# crowbar.net
KiCad netlist of a schematic drawn in Altium Designer
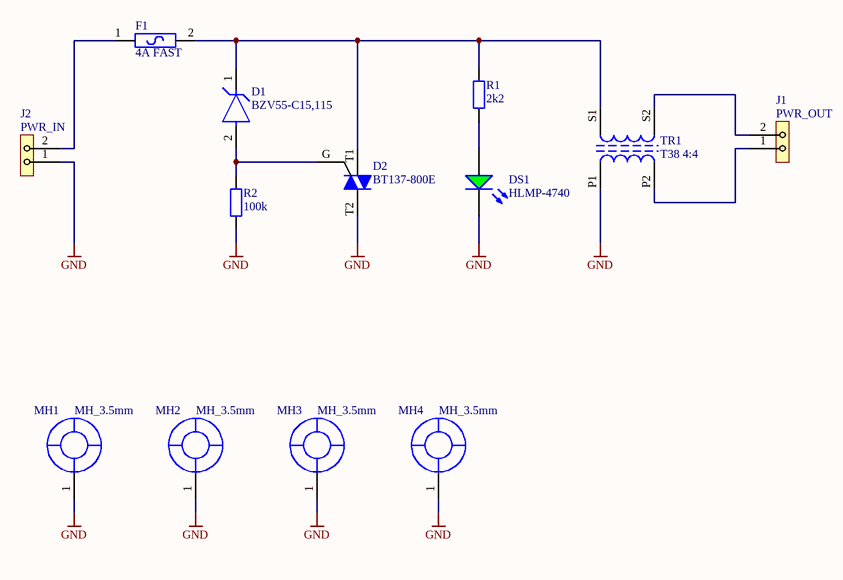
[diagram p0: crowbar.SchDoc]

(export (version "E")
  (design (tool "Eeschema 10.0.6"))
  (components
    (comp (ref "D1")
      (value "BZV55-C15,115")
      (footprint "FP-SOD80C-MFG")
      (description "DIODE ZENER 15V 500MW LLDS")
      (libsource (lib "Altium Content Vault") (part "f813f71cba58e380607f5dd3caf9714"))
    )
    (comp (ref "D2")
      (value "BT137-800E")
      (footprint "DPAK254P1525X460-3N")
      (libsource (lib "COMM_SHIELD_STUFF") (part "Triac"))
    )
    (comp (ref "DS1")
      (value "HLMP-4740")
      (footprint "AVAG-HLMP-4740")
      (description "T-1 3/4 (5 mm) Low Current LED Lamp, Green, 1.9 V, -20 to 100 degC, 2-Pin THD, RoHS, Bulk")
      (fields (field (name "MANUFACTURER") "AvagoTechnologies"))
      (libsource (lib "Altium Content Vault") (part "LED-GREEN-AK-2"))
    )
    (comp (ref "F1")
      (value "4A FAST")
      (footprint "FUSE_SOCKET_PTF/78")
      (libsource (lib "COMM_SHIELD_STUFF") (part "FUSE"))
    )
    (comp (ref "J1")
      (value "PWR_OUT")
      (footprint "SOLDER_PAD_1L_2P")
      (libsource (lib "") (part "SOLDER_PAD_1_2P_1"))
    )
    (comp (ref "J2")
      (value "PWR_IN")
      (footprint "SOLDER_PAD_1L_2P")
      (libsource (lib "COMM_SHIELD_STUFF") (part "SOLDER_PAD_1_2P"))
    )
    (comp (ref "MH1")
      (value "MH_3.5mm")
      (footprint "MOUNTING_HOLE_GROUNDED")
      (description "3.5mm grounded mounting hole")
      (libsource (lib "COMM_SHIELD_STUFF") (part "MOUNTING_HOLE_3.5mm_1"))
    )
    (comp (ref "MH2")
      (value "MH_3.5mm")
      (footprint "MOUNTING_HOLE_GROUNDED")
      (description "3.5mm grounded mounting hole")
      (libsource (lib "COMM_SHIELD_STUFF") (part "MOUNTING_HOLE_3.5mm_1"))
    )
    (comp (ref "MH3")
      (value "MH_3.5mm")
      (footprint "MOUNTING_HOLE_GROUNDED")
      (description "3.5mm grounded mounting hole")
      (libsource (lib "COMM_SHIELD_STUFF") (part "MOUNTING_HOLE_3.5mm_1"))
    )
    (comp (ref "MH4")
      (value "MH_3.5mm")
      (footprint "MOUNTING_HOLE_GROUNDED")
      (description "3.5mm grounded mounting hole")
      (libsource (lib "COMM_SHIELD_STUFF") (part "MOUNTING_HOLE_3.5mm_1"))
    )
    (comp (ref "R1")
      (value "Resistor")
      (footprint "FP-CRCW1206-e3-IPC_B")
      (description "EU symbol")
      (fields (field (name "RESISTANCE") "2k2"))
      (libsource (lib "COMM_SHIELD_STUFF") (part "Resistor"))
    )
    (comp (ref "R2")
      (value "Resistor")
      (footprint "FP-CRCW1206-e3-IPC_B")
      (description "EU symbol")
      (fields (field (name "RESISTANCE") "100k"))
      (libsource (lib "COMM_SHIELD_STUFF") (part "Resistor"))
    )
    (comp (ref "TR1")
      (value "T38 4:4")
      (footprint "TRANSFORMER_TOROID_FLAT")
      (description "1 Primer; 1 Seconder")
      (libsource (lib "COMM_SHIELD_STUFF") (part "Transformer"))
    )
  )
  (nets
    (net (code "1") (name "GND") (class "Default")
      (node (ref "D2") (pin "T2") (pinfunction "T2_T2") (pintype "passive"))
      (node (ref "DS1") (pin "2") (pinfunction "K_2") (pintype "passive"))
      (node (ref "J2") (pin "1") (pinfunction "1_1") (pintype "passive"))
      (node (ref "MH1") (pin "1") (pinfunction "1_1") (pintype "passive"))
      (node (ref "MH2") (pin "1") (pinfunction "1_1") (pintype "passive"))
      (node (ref "MH3") (pin "1") (pinfunction "1_1") (pintype "passive"))
      (node (ref "MH4") (pin "1") (pinfunction "1_1") (pintype "passive"))
      (node (ref "R2") (pin "2") (pinfunction "2_2") (pintype "passive"))
      (node (ref "TR1") (pin "P1") (pinfunction "P1_P1") (pintype "passive"))
    )
    (net (code "2") (name "Net-(D1-A)") (class "Default")
      (node (ref "D1") (pin "2") (pinfunction "A_2") (pintype "passive"))
      (node (ref "D2") (pin "G") (pinfunction "G_G") (pintype "passive"))
      (node (ref "R2") (pin "1") (pinfunction "1_1") (pintype "passive"))
    )
    (net (code "3") (name "Net-(D1-C)") (class "Default")
      (node (ref "D1") (pin "1") (pinfunction "C_1") (pintype "passive"))
      (node (ref "D2") (pin "T1") (pinfunction "T1_T1") (pintype "passive"))
      (node (ref "F1") (pin "2") (pinfunction "2_2") (pintype "passive"))
      (node (ref "R1") (pin "1") (pinfunction "1_1") (pintype "passive"))
      (node (ref "TR1") (pin "S1") (pinfunction "S1_S1") (pintype "passive"))
    )
    (net (code "4") (name "Net-(DS1-A)") (class "Default")
      (node (ref "DS1") (pin "1") (pinfunction "A_1") (pintype "passive"))
      (node (ref "R1") (pin "2") (pinfunction "2_2") (pintype "passive"))
    )
    (net (code "5") (name "Net-(F1-Pad1)") (class "Default")
      (node (ref "F1") (pin "1") (pinfunction "1_1") (pintype "passive"))
      (node (ref "J2") (pin "2") (pinfunction "2_2") (pintype "passive"))
    )
    (net (code "6") (name "Net-(J1-Pad1)") (class "Default")
      (node (ref "J1") (pin "1") (pinfunction "1_1") (pintype "passive"))
      (node (ref "TR1") (pin "P2") (pinfunction "P2_P2") (pintype "passive"))
    )
    (net (code "7") (name "Net-(J1-Pad2)") (class "Default")
      (node (ref "J1") (pin "2") (pinfunction "2_2") (pintype "passive"))
      (node (ref "TR1") (pin "S2") (pinfunction "S2_S2") (pintype "passive"))
    )
  )
)
